# 77seg.net
KiCad netlist of a schematic drawn in EAGLE
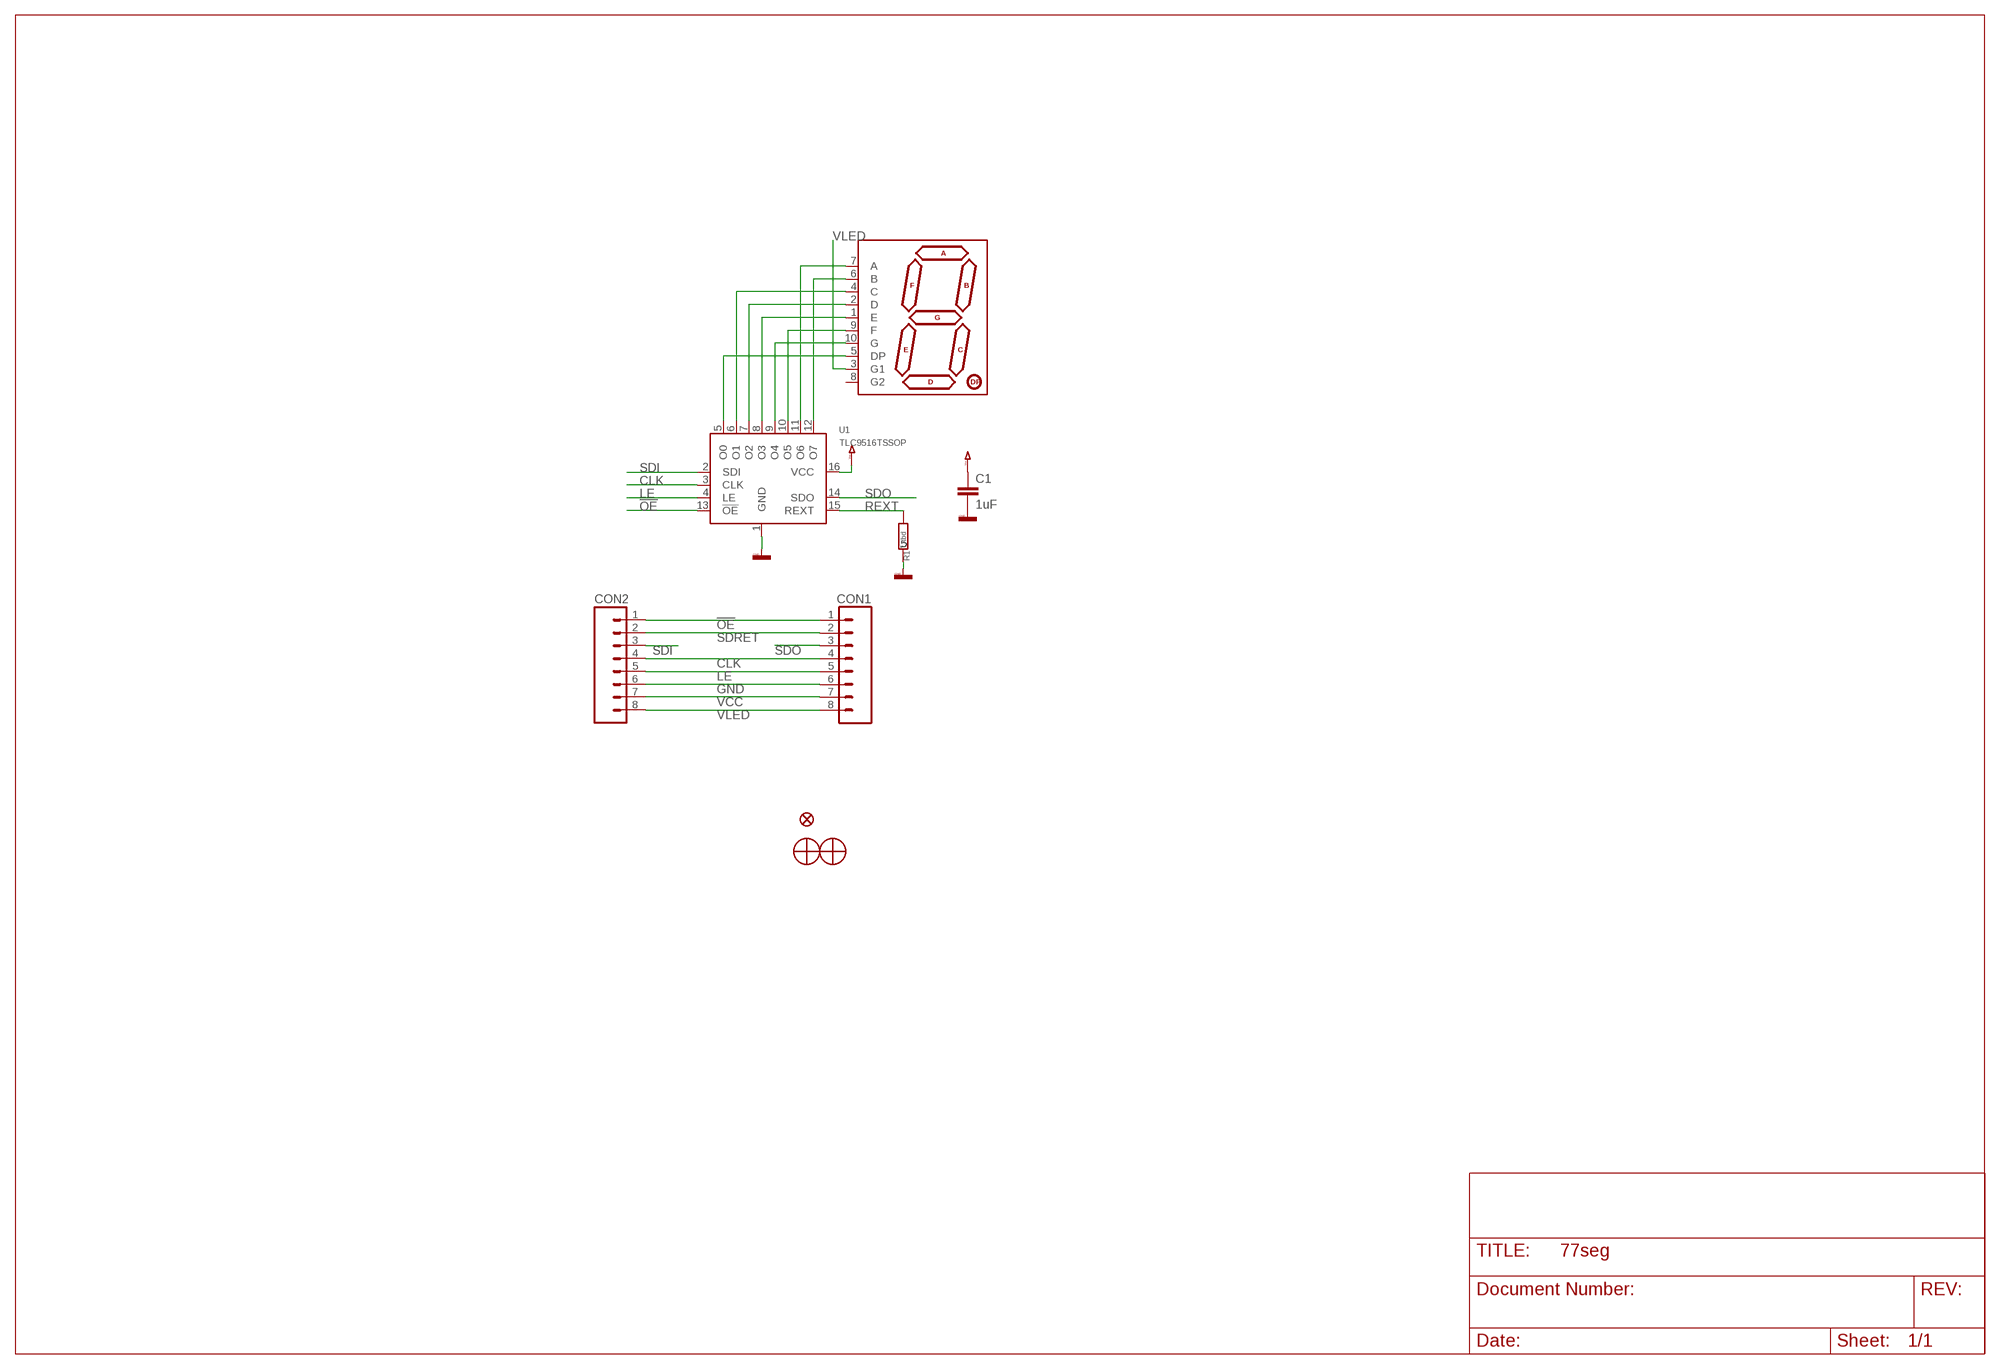
[diagram p0: schematic, sheet 1]

(export (version "E")
  (design (tool "Eeschema 10.0.6"))
  (components
    (comp (ref "C1")
      (value "1uF")
      (footprint "eagle-import:C0603")
      (libsource (lib "eagle-import") (part "CAP_0603"))
    )
    (comp (ref "CON1")
      (value "M081.27MM_NO1")
      (footprint "eagle-import:1X08_1.27MM_NO1")
      (libsource (lib "eagle-import") (part "M081.27MM_NO1"))
    )
    (comp (ref "CON2")
      (value "M081.27MM_NO1")
      (footprint "eagle-import:1X08_1.27MM_NO1")
      (libsource (lib "eagle-import") (part "M081.27MM_NO1"))
    )
    (comp (ref "JP1")
      (value "FIDUCIAL1X1.5")
      (footprint "eagle-import:FIDUCIAL_1X1.5")
      (libsource (lib "eagle-import") (part "FIDUCIAL1X1.5"))
    )
    (comp (ref "R1")
      (value "tbd")
      (footprint "eagle-import:R0603")
      (libsource (lib "eagle-import") (part "RESISTOR_0603"))
    )
    (comp (ref "U$1")
      (value "7-SEGMENT-DISPLAYPTH")
      (footprint "eagle-import:7-SEGMENT-DISPLAY")
      (libsource (lib "eagle-import") (part "7-SEGMENT-DISPLAYPTH"))
    )
    (comp (ref "U$2")
      (value "SCREW_NOGND")
      (footprint "eagle-import:SCREW_M2_NOVIAS")
      (libsource (lib "eagle-import") (part "SCREW_NOGND"))
    )
    (comp (ref "U$3")
      (value "SCREW_NOGND")
      (footprint "eagle-import:SCREW_M2_NOVIAS")
      (libsource (lib "eagle-import") (part "SCREW_NOGND"))
    )
    (comp (ref "U1")
      (value "TLC9516TSSOP")
      (footprint "eagle-import:TSSOP16")
      (libsource (lib "eagle-import") (part "TLC9516TSSOP"))
    )
  )
  (nets
    (net (code "1") (name "/CLK") (class "Default")
      (node (ref "CON1") (pin "4") (pinfunction "4_4") (pintype "passive"))
      (node (ref "CON2") (pin "4") (pinfunction "4_4") (pintype "passive"))
      (node (ref "U1") (pin "3") (pinfunction "CLK_3") (pintype "input"))
    )
    (net (code "2") (name "/LE") (class "Default")
      (node (ref "CON1") (pin "5") (pinfunction "5_5") (pintype "passive"))
      (node (ref "CON2") (pin "5") (pinfunction "5_5") (pintype "passive"))
      (node (ref "U1") (pin "4") (pinfunction "LE_4") (pintype "input"))
    )
    (net (code "3") (name "/REXT") (class "Default")
      (node (ref "R1") (pin "1") (pinfunction "1_1") (pintype "passive"))
      (node (ref "U1") (pin "15") (pinfunction "REXT_15") (pintype "input"))
    )
    (net (code "4") (name "/SDI") (class "Default")
      (node (ref "CON2") (pin "3") (pinfunction "3_3") (pintype "passive"))
      (node (ref "U1") (pin "2") (pinfunction "SDI_2") (pintype "input"))
    )
    (net (code "5") (name "/SDO") (class "Default")
      (node (ref "CON1") (pin "3") (pinfunction "3_3") (pintype "passive"))
      (node (ref "U1") (pin "14") (pinfunction "SDO_14") (pintype "output"))
    )
    (net (code "6") (name "/SDRET") (class "Default")
      (node (ref "CON1") (pin "2") (pinfunction "2_2") (pintype "passive"))
      (node (ref "CON2") (pin "2") (pinfunction "2_2") (pintype "passive"))
    )
    (net (code "7") (name "/VLED") (class "Default")
      (node (ref "CON1") (pin "8") (pinfunction "8_8") (pintype "passive"))
      (node (ref "CON2") (pin "8") (pinfunction "8_8") (pintype "passive"))
      (node (ref "U$1") (pin "3") (pinfunction "G1_3") (pintype "bidirectional"))
    )
    (net (code "8") (name "/~{OE}") (class "Default")
      (node (ref "CON1") (pin "1") (pinfunction "1_1") (pintype "passive"))
      (node (ref "CON2") (pin "1") (pinfunction "1_1") (pintype "passive"))
      (node (ref "U1") (pin "13") (pinfunction "~{OE}_13") (pintype "input"))
    )
    (net (code "9") (name "GND") (class "Default")
      (node (ref "C1") (pin "2") (pinfunction "2_2") (pintype "passive"))
      (node (ref "CON1") (pin "6") (pinfunction "6_6") (pintype "passive"))
      (node (ref "CON2") (pin "6") (pinfunction "6_6") (pintype "passive"))
      (node (ref "R1") (pin "2") (pinfunction "2_2") (pintype "passive"))
      (node (ref "U1") (pin "1") (pinfunction "GND_1") (pintype "power_in"))
    )
    (net (code "10") (name "Net-(U$1-A)") (class "Default")
      (node (ref "U$1") (pin "7") (pinfunction "A_7") (pintype "bidirectional"))
      (node (ref "U1") (pin "11") (pinfunction "O6_11") (pintype "input"))
    )
    (net (code "11") (name "Net-(U$1-B)") (class "Default")
      (node (ref "U$1") (pin "6") (pinfunction "B_6") (pintype "bidirectional"))
      (node (ref "U1") (pin "12") (pinfunction "O7_12") (pintype "input"))
    )
    (net (code "12") (name "Net-(U$1-C)") (class "Default")
      (node (ref "U$1") (pin "4") (pinfunction "C_4") (pintype "bidirectional"))
      (node (ref "U1") (pin "6") (pinfunction "O1_6") (pintype "input"))
    )
    (net (code "13") (name "Net-(U$1-D)") (class "Default")
      (node (ref "U$1") (pin "2") (pinfunction "D_2") (pintype "bidirectional"))
      (node (ref "U1") (pin "7") (pinfunction "O2_7") (pintype "input"))
    )
    (net (code "14") (name "Net-(U$1-DP)") (class "Default")
      (node (ref "U$1") (pin "5") (pinfunction "DP_5") (pintype "bidirectional"))
      (node (ref "U1") (pin "5") (pinfunction "O0_5") (pintype "input"))
    )
    (net (code "15") (name "Net-(U$1-E)") (class "Default")
      (node (ref "U$1") (pin "1") (pinfunction "E_1") (pintype "bidirectional"))
      (node (ref "U1") (pin "8") (pinfunction "O3_8") (pintype "input"))
    )
    (net (code "16") (name "Net-(U$1-F)") (class "Default")
      (node (ref "U$1") (pin "9") (pinfunction "F_9") (pintype "bidirectional"))
      (node (ref "U1") (pin "10") (pinfunction "O5_10") (pintype "input"))
    )
    (net (code "17") (name "Net-(U$1-G)") (class "Default")
      (node (ref "U$1") (pin "10") (pinfunction "G_10") (pintype "bidirectional"))
      (node (ref "U1") (pin "9") (pinfunction "O4_9") (pintype "input"))
    )
    (net (code "18") (name "VCC") (class "Default")
      (node (ref "C1") (pin "1") (pinfunction "1_1") (pintype "passive"))
      (node (ref "CON1") (pin "7") (pinfunction "7_7") (pintype "passive"))
      (node (ref "CON2") (pin "7") (pinfunction "7_7") (pintype "passive"))
      (node (ref "U1") (pin "16") (pinfunction "VCC_16") (pintype "power_in"))
    )
    (net (code "19") (name "unconnected-(U$1-G2-Pad8)") (class "Default")
      (node (ref "U$1") (pin "8") (pinfunction "G2_8") (pintype "bidirectional"))
    )
  )
)
